# MiniTest.net
KiCad netlist of a schematic drawn in EAGLE
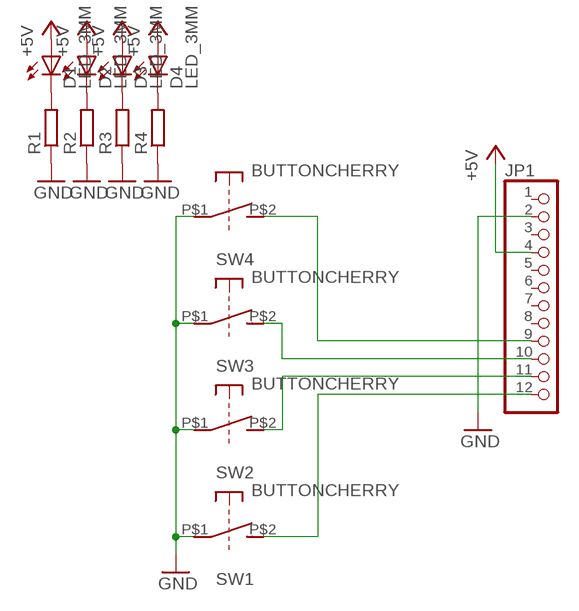
[diagram p0: schematic, sheet 1]

(export (version "E")
  (design (tool "Eeschema 10.0.6"))
  (components
    (comp (ref "D1")
      (value "LED_3MM")
      (footprint "eagle-import:LED3MM")
      (libsource (lib "eagle-import") (part "LED_3MM"))
    )
    (comp (ref "D2")
      (value "LED_3MM")
      (footprint "eagle-import:LED3MM")
      (libsource (lib "eagle-import") (part "LED_3MM"))
    )
    (comp (ref "D3")
      (value "LED_3MM")
      (footprint "eagle-import:LED3MM")
      (libsource (lib "eagle-import") (part "LED_3MM"))
    )
    (comp (ref "D4")
      (value "LED_3MM")
      (footprint "eagle-import:LED3MM")
      (libsource (lib "eagle-import") (part "LED_3MM"))
    )
    (comp (ref "JP1")
      (value "PINHD-1X12")
      (footprint "eagle-import:1X12")
      (libsource (lib "eagle-import") (part "PINHD-1X12"))
    )
    (comp (ref "R1")
      (value "R_R1206")
      (footprint "eagle-import:RESC3216X60")
      (libsource (lib "eagle-import") (part "R_R1206"))
    )
    (comp (ref "R2")
      (value "R_R1206")
      (footprint "eagle-import:RESC3216X60")
      (libsource (lib "eagle-import") (part "R_R1206"))
    )
    (comp (ref "R3")
      (value "R_R1206")
      (footprint "eagle-import:RESC3216X60")
      (libsource (lib "eagle-import") (part "R_R1206"))
    )
    (comp (ref "R4")
      (value "R_R1206")
      (footprint "eagle-import:RESC3216X60")
      (libsource (lib "eagle-import") (part "R_R1206"))
    )
    (comp (ref "SW1")
      (value "BUTTONCHERRY")
      (footprint "eagle-import:SW_GATERON")
      (libsource (lib "eagle-import") (part "BUTTONCHERRY"))
    )
    (comp (ref "SW2")
      (value "BUTTONCHERRY")
      (footprint "eagle-import:SW_GATERON")
      (libsource (lib "eagle-import") (part "BUTTONCHERRY"))
    )
    (comp (ref "SW3")
      (value "BUTTONCHERRY")
      (footprint "eagle-import:SW_GATERON")
      (libsource (lib "eagle-import") (part "BUTTONCHERRY"))
    )
    (comp (ref "SW4")
      (value "BUTTONCHERRY")
      (footprint "eagle-import:SW_GATERON")
      (libsource (lib "eagle-import") (part "BUTTONCHERRY"))
    )
  )
  (nets
    (net (code "1") (name "+5V") (class "Default")
      (node (ref "D1") (pin "A") (pinfunction "A_A") (pintype "passive"))
      (node (ref "D2") (pin "A") (pinfunction "A_A") (pintype "passive"))
      (node (ref "D3") (pin "A") (pinfunction "A_A") (pintype "passive"))
      (node (ref "D4") (pin "A") (pinfunction "A_A") (pintype "passive"))
      (node (ref "JP1") (pin "4") (pinfunction "4_4") (pintype "passive"))
    )
    (net (code "2") (name "GND") (class "Default")
      (node (ref "JP1") (pin "2") (pinfunction "2_2") (pintype "passive"))
      (node (ref "R1") (pin "1") (pinfunction "1_1") (pintype "passive"))
      (node (ref "R2") (pin "1") (pinfunction "1_1") (pintype "passive"))
      (node (ref "R3") (pin "1") (pinfunction "1_1") (pintype "passive"))
      (node (ref "R4") (pin "1") (pinfunction "1_1") (pintype "passive"))
      (node (ref "SW1") (pin "P$1") (pinfunction "1_P$1") (pintype "passive"))
      (node (ref "SW2") (pin "P$1") (pinfunction "1_P$1") (pintype "passive"))
      (node (ref "SW3") (pin "P$1") (pinfunction "1_P$1") (pintype "passive"))
      (node (ref "SW4") (pin "P$1") (pinfunction "1_P$1") (pintype "passive"))
    )
    (net (code "3") (name "Net-(D1-C)") (class "Default")
      (node (ref "D1") (pin "K") (pinfunction "C_K") (pintype "passive"))
      (node (ref "R1") (pin "2") (pinfunction "2_2") (pintype "passive"))
    )
    (net (code "4") (name "Net-(D2-C)") (class "Default")
      (node (ref "D2") (pin "K") (pinfunction "C_K") (pintype "passive"))
      (node (ref "R2") (pin "2") (pinfunction "2_2") (pintype "passive"))
    )
    (net (code "5") (name "Net-(D3-C)") (class "Default")
      (node (ref "D3") (pin "K") (pinfunction "C_K") (pintype "passive"))
      (node (ref "R3") (pin "2") (pinfunction "2_2") (pintype "passive"))
    )
    (net (code "6") (name "Net-(D4-C)") (class "Default")
      (node (ref "D4") (pin "K") (pinfunction "C_K") (pintype "passive"))
      (node (ref "R4") (pin "2") (pinfunction "2_2") (pintype "passive"))
    )
    (net (code "7") (name "Net-(SW1-2)") (class "Default")
      (node (ref "JP1") (pin "12") (pinfunction "12_12") (pintype "passive"))
      (node (ref "SW1") (pin "P$2") (pinfunction "2_P$2") (pintype "passive"))
    )
    (net (code "8") (name "Net-(SW2-2)") (class "Default")
      (node (ref "JP1") (pin "11") (pinfunction "11_11") (pintype "passive"))
      (node (ref "SW2") (pin "P$2") (pinfunction "2_P$2") (pintype "passive"))
    )
    (net (code "9") (name "Net-(SW3-2)") (class "Default")
      (node (ref "JP1") (pin "10") (pinfunction "10_10") (pintype "passive"))
      (node (ref "SW3") (pin "P$2") (pinfunction "2_P$2") (pintype "passive"))
    )
    (net (code "10") (name "Net-(SW4-2)") (class "Default")
      (node (ref "JP1") (pin "9") (pinfunction "9_9") (pintype "passive"))
      (node (ref "SW4") (pin "P$2") (pinfunction "2_P$2") (pintype "passive"))
    )
    (net (code "11") (name "unconnected-(JP1-Pad1)") (class "Default")
      (node (ref "JP1") (pin "1") (pinfunction "1_1") (pintype "passive"))
    )
    (net (code "12") (name "unconnected-(JP1-Pad3)") (class "Default")
      (node (ref "JP1") (pin "3") (pinfunction "3_3") (pintype "passive"))
    )
    (net (code "13") (name "unconnected-(JP1-Pad5)") (class "Default")
      (node (ref "JP1") (pin "5") (pinfunction "5_5") (pintype "passive"))
    )
    (net (code "14") (name "unconnected-(JP1-Pad6)") (class "Default")
      (node (ref "JP1") (pin "6") (pinfunction "6_6") (pintype "passive"))
    )
    (net (code "15") (name "unconnected-(JP1-Pad7)") (class "Default")
      (node (ref "JP1") (pin "7") (pinfunction "7_7") (pintype "passive"))
    )
    (net (code "16") (name "unconnected-(JP1-Pad8)") (class "Default")
      (node (ref "JP1") (pin "8") (pinfunction "8_8") (pintype "passive"))
    )
  )
)
